# QuadWing_2x2.net
KiCad netlist of a schematic drawn in EAGLE
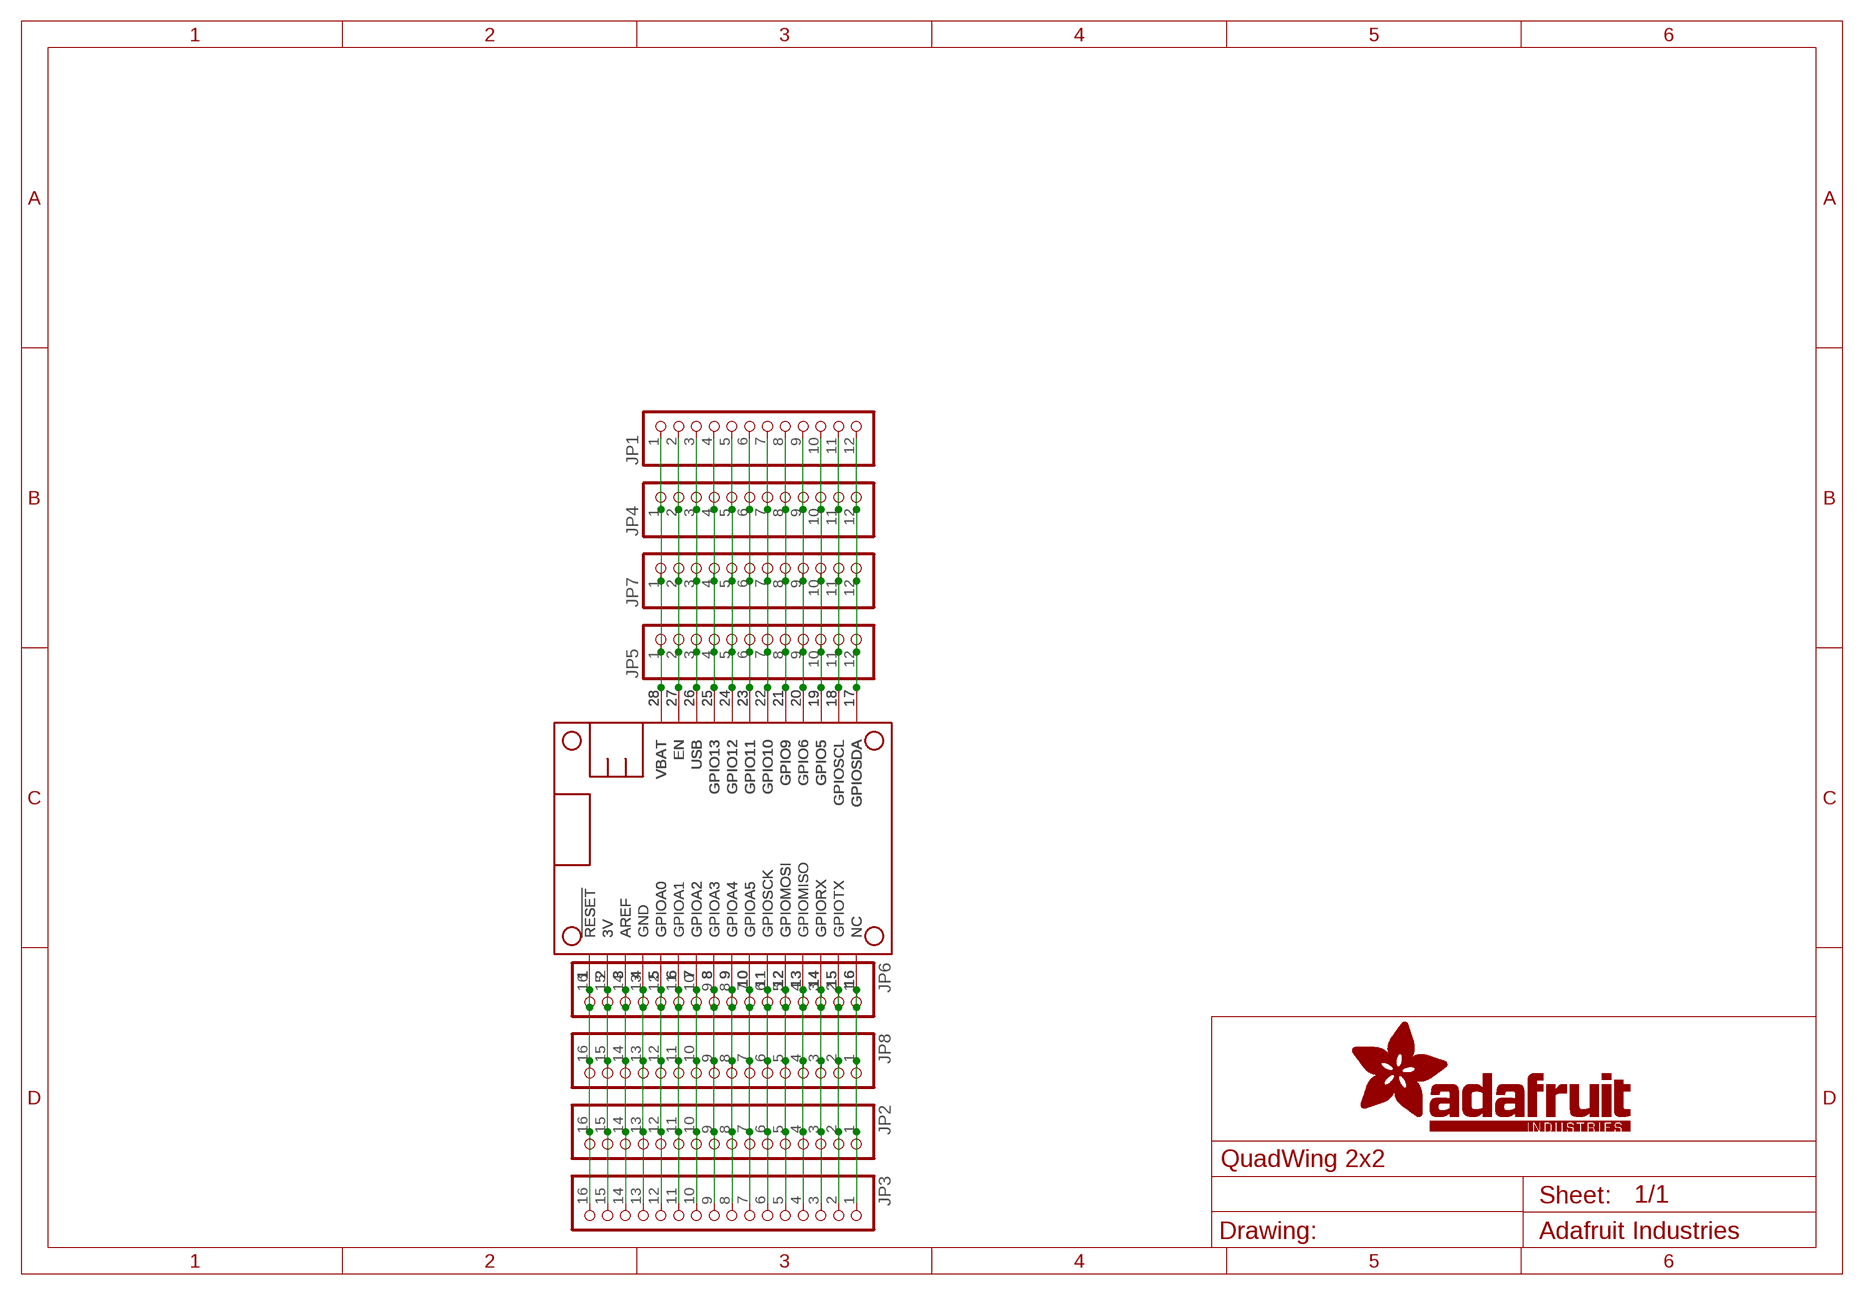
[diagram p0: schematic, sheet 1]

(export (version "E")
  (design (tool "Eeschema 10.0.6"))
  (components
    (comp (ref "JP1")
      (value "HEADER-1X1276MIL")
      (footprint "eagle-import:1X12_ROUND_76MIL")
      (libsource (lib "eagle-import") (part "HEADER-1X1276MIL"))
    )
    (comp (ref "JP2")
      (value "HEADER-1X16_76MIL")
      (footprint "eagle-import:1X16_ROUND_76MIL")
      (libsource (lib "eagle-import") (part "HEADER-1X16_76MIL"))
    )
    (comp (ref "JP3")
      (value "HEADER-1X16_76MIL")
      (footprint "eagle-import:1X16_ROUND_76MIL")
      (libsource (lib "eagle-import") (part "HEADER-1X16_76MIL"))
    )
    (comp (ref "JP4")
      (value "HEADER-1X1276MIL")
      (footprint "eagle-import:1X12_ROUND_76MIL")
      (libsource (lib "eagle-import") (part "HEADER-1X1276MIL"))
    )
    (comp (ref "JP5")
      (value "HEADER-1X1276MIL")
      (footprint "eagle-import:1X12_ROUND_76MIL")
      (libsource (lib "eagle-import") (part "HEADER-1X1276MIL"))
    )
    (comp (ref "JP6")
      (value "HEADER-1X16_76MIL")
      (footprint "eagle-import:1X16_ROUND_76MIL")
      (libsource (lib "eagle-import") (part "HEADER-1X16_76MIL"))
    )
    (comp (ref "JP7")
      (value "HEADER-1X1276MIL")
      (footprint "eagle-import:1X12_ROUND_76MIL")
      (libsource (lib "eagle-import") (part "HEADER-1X1276MIL"))
    )
    (comp (ref "JP8")
      (value "HEADER-1X16_76MIL")
      (footprint "eagle-import:1X16_ROUND_76MIL")
      (libsource (lib "eagle-import") (part "HEADER-1X16_76MIL"))
    )
    (comp (ref "MS1")
      (value "FEATHERWING_NODIM")
      (footprint "eagle-import:FEATHERWING_DIM")
      (libsource (lib "eagle-import") (part "FEATHERWING_NODIM"))
    )
    (comp (ref "MS2")
      (value "FEATHERWING_NODIM")
      (footprint "eagle-import:FEATHERWING_DIM")
      (libsource (lib "eagle-import") (part "FEATHERWING_NODIM"))
    )
    (comp (ref "MS3")
      (value "FEATHERWING_NODIM")
      (footprint "eagle-import:FEATHERWING_DIM")
      (libsource (lib "eagle-import") (part "FEATHERWING_NODIM"))
    )
    (comp (ref "MS4")
      (value "FEATHERWING_NODIM")
      (footprint "eagle-import:FEATHERWING_DIM")
      (libsource (lib "eagle-import") (part "FEATHERWING_NODIM"))
    )
  )
  (nets
    (net (code "1") (name "Net-(MS1-3V)") (class "Default")
      (node (ref "JP2") (pin "15") (pinfunction "15_15") (pintype "passive"))
      (node (ref "JP3") (pin "15") (pinfunction "15_15") (pintype "passive"))
      (node (ref "JP6") (pin "15") (pinfunction "15_15") (pintype "passive"))
      (node (ref "JP8") (pin "15") (pinfunction "15_15") (pintype "passive"))
      (node (ref "MS1") (pin "2") (pinfunction "3V_2") (pintype "power_in"))
      (node (ref "MS2") (pin "2") (pinfunction "3V_2") (pintype "power_in"))
      (node (ref "MS3") (pin "2") (pinfunction "3V_2") (pintype "power_in"))
      (node (ref "MS4") (pin "2") (pinfunction "3V_2") (pintype "power_in"))
    )
    (net (code "2") (name "Net-(MS1-AREF)") (class "Default")
      (node (ref "JP2") (pin "14") (pinfunction "14_14") (pintype "passive"))
      (node (ref "JP3") (pin "14") (pinfunction "14_14") (pintype "passive"))
      (node (ref "JP6") (pin "14") (pinfunction "14_14") (pintype "passive"))
      (node (ref "JP8") (pin "14") (pinfunction "14_14") (pintype "passive"))
      (node (ref "MS1") (pin "3") (pinfunction "AREF_3") (pintype "passive"))
      (node (ref "MS2") (pin "3") (pinfunction "AREF_3") (pintype "passive"))
      (node (ref "MS3") (pin "3") (pinfunction "AREF_3") (pintype "passive"))
      (node (ref "MS4") (pin "3") (pinfunction "AREF_3") (pintype "passive"))
    )
    (net (code "3") (name "Net-(MS1-EN)") (class "Default")
      (node (ref "JP1") (pin "2") (pinfunction "2_2") (pintype "passive"))
      (node (ref "JP4") (pin "2") (pinfunction "2_2") (pintype "passive"))
      (node (ref "JP5") (pin "2") (pinfunction "2_2") (pintype "passive"))
      (node (ref "JP7") (pin "2") (pinfunction "2_2") (pintype "passive"))
      (node (ref "MS1") (pin "27") (pinfunction "EN_27") (pintype "passive"))
      (node (ref "MS2") (pin "27") (pinfunction "EN_27") (pintype "passive"))
      (node (ref "MS3") (pin "27") (pinfunction "EN_27") (pintype "passive"))
      (node (ref "MS4") (pin "27") (pinfunction "EN_27") (pintype "passive"))
    )
    (net (code "4") (name "Net-(MS1-GND)") (class "Default")
      (node (ref "JP2") (pin "13") (pinfunction "13_13") (pintype "passive"))
      (node (ref "JP3") (pin "13") (pinfunction "13_13") (pintype "passive"))
      (node (ref "JP6") (pin "13") (pinfunction "13_13") (pintype "passive"))
      (node (ref "JP8") (pin "13") (pinfunction "13_13") (pintype "passive"))
      (node (ref "MS1") (pin "4") (pinfunction "GND_4") (pintype "power_in"))
      (node (ref "MS2") (pin "4") (pinfunction "GND_4") (pintype "power_in"))
      (node (ref "MS3") (pin "4") (pinfunction "GND_4") (pintype "power_in"))
      (node (ref "MS4") (pin "4") (pinfunction "GND_4") (pintype "power_in"))
    )
    (net (code "5") (name "Net-(MS1-GPIO5)") (class "Default")
      (node (ref "JP1") (pin "10") (pinfunction "10_10") (pintype "passive"))
      (node (ref "JP4") (pin "10") (pinfunction "10_10") (pintype "passive"))
      (node (ref "JP5") (pin "10") (pinfunction "10_10") (pintype "passive"))
      (node (ref "JP7") (pin "10") (pinfunction "10_10") (pintype "passive"))
      (node (ref "MS1") (pin "19") (pinfunction "GPIO5_19") (pintype "bidirectional"))
      (node (ref "MS2") (pin "19") (pinfunction "GPIO5_19") (pintype "bidirectional"))
      (node (ref "MS3") (pin "19") (pinfunction "GPIO5_19") (pintype "bidirectional"))
      (node (ref "MS4") (pin "19") (pinfunction "GPIO5_19") (pintype "bidirectional"))
    )
    (net (code "6") (name "Net-(MS1-GPIO6)") (class "Default")
      (node (ref "JP1") (pin "9") (pinfunction "9_9") (pintype "passive"))
      (node (ref "JP4") (pin "9") (pinfunction "9_9") (pintype "passive"))
      (node (ref "JP5") (pin "9") (pinfunction "9_9") (pintype "passive"))
      (node (ref "JP7") (pin "9") (pinfunction "9_9") (pintype "passive"))
      (node (ref "MS1") (pin "20") (pinfunction "GPIO6_20") (pintype "bidirectional"))
      (node (ref "MS2") (pin "20") (pinfunction "GPIO6_20") (pintype "bidirectional"))
      (node (ref "MS3") (pin "20") (pinfunction "GPIO6_20") (pintype "bidirectional"))
      (node (ref "MS4") (pin "20") (pinfunction "GPIO6_20") (pintype "bidirectional"))
    )
    (net (code "7") (name "Net-(MS1-GPIO9)") (class "Default")
      (node (ref "JP1") (pin "8") (pinfunction "8_8") (pintype "passive"))
      (node (ref "JP4") (pin "8") (pinfunction "8_8") (pintype "passive"))
      (node (ref "JP5") (pin "8") (pinfunction "8_8") (pintype "passive"))
      (node (ref "JP7") (pin "8") (pinfunction "8_8") (pintype "passive"))
      (node (ref "MS1") (pin "21") (pinfunction "GPIO9_21") (pintype "bidirectional"))
      (node (ref "MS2") (pin "21") (pinfunction "GPIO9_21") (pintype "bidirectional"))
      (node (ref "MS3") (pin "21") (pinfunction "GPIO9_21") (pintype "bidirectional"))
      (node (ref "MS4") (pin "21") (pinfunction "GPIO9_21") (pintype "bidirectional"))
    )
    (net (code "8") (name "Net-(MS1-GPIO10)") (class "Default")
      (node (ref "JP1") (pin "7") (pinfunction "7_7") (pintype "passive"))
      (node (ref "JP4") (pin "7") (pinfunction "7_7") (pintype "passive"))
      (node (ref "JP5") (pin "7") (pinfunction "7_7") (pintype "passive"))
      (node (ref "JP7") (pin "7") (pinfunction "7_7") (pintype "passive"))
      (node (ref "MS1") (pin "22") (pinfunction "GPIO10_22") (pintype "bidirectional"))
      (node (ref "MS2") (pin "22") (pinfunction "GPIO10_22") (pintype "bidirectional"))
      (node (ref "MS3") (pin "22") (pinfunction "GPIO10_22") (pintype "bidirectional"))
      (node (ref "MS4") (pin "22") (pinfunction "GPIO10_22") (pintype "bidirectional"))
    )
    (net (code "9") (name "Net-(MS1-GPIO11)") (class "Default")
      (node (ref "JP1") (pin "6") (pinfunction "6_6") (pintype "passive"))
      (node (ref "JP4") (pin "6") (pinfunction "6_6") (pintype "passive"))
      (node (ref "JP5") (pin "6") (pinfunction "6_6") (pintype "passive"))
      (node (ref "JP7") (pin "6") (pinfunction "6_6") (pintype "passive"))
      (node (ref "MS1") (pin "23") (pinfunction "GPIO11_23") (pintype "bidirectional"))
      (node (ref "MS2") (pin "23") (pinfunction "GPIO11_23") (pintype "bidirectional"))
      (node (ref "MS3") (pin "23") (pinfunction "GPIO11_23") (pintype "bidirectional"))
      (node (ref "MS4") (pin "23") (pinfunction "GPIO11_23") (pintype "bidirectional"))
    )
    (net (code "10") (name "Net-(MS1-GPIO12)") (class "Default")
      (node (ref "JP1") (pin "5") (pinfunction "5_5") (pintype "passive"))
      (node (ref "JP4") (pin "5") (pinfunction "5_5") (pintype "passive"))
      (node (ref "JP5") (pin "5") (pinfunction "5_5") (pintype "passive"))
      (node (ref "JP7") (pin "5") (pinfunction "5_5") (pintype "passive"))
      (node (ref "MS1") (pin "24") (pinfunction "GPIO12_24") (pintype "bidirectional"))
      (node (ref "MS2") (pin "24") (pinfunction "GPIO12_24") (pintype "bidirectional"))
      (node (ref "MS3") (pin "24") (pinfunction "GPIO12_24") (pintype "bidirectional"))
      (node (ref "MS4") (pin "24") (pinfunction "GPIO12_24") (pintype "bidirectional"))
    )
    (net (code "11") (name "Net-(MS1-GPIO13)") (class "Default")
      (node (ref "JP1") (pin "4") (pinfunction "4_4") (pintype "passive"))
      (node (ref "JP4") (pin "4") (pinfunction "4_4") (pintype "passive"))
      (node (ref "JP5") (pin "4") (pinfunction "4_4") (pintype "passive"))
      (node (ref "JP7") (pin "4") (pinfunction "4_4") (pintype "passive"))
      (node (ref "MS1") (pin "25") (pinfunction "GPIO13_25") (pintype "bidirectional"))
      (node (ref "MS2") (pin "25") (pinfunction "GPIO13_25") (pintype "bidirectional"))
      (node (ref "MS3") (pin "25") (pinfunction "GPIO13_25") (pintype "bidirectional"))
      (node (ref "MS4") (pin "25") (pinfunction "GPIO13_25") (pintype "bidirectional"))
    )
    (net (code "12") (name "Net-(MS1-GPIOA0)") (class "Default")
      (node (ref "JP2") (pin "12") (pinfunction "12_12") (pintype "passive"))
      (node (ref "JP3") (pin "12") (pinfunction "12_12") (pintype "passive"))
      (node (ref "JP6") (pin "12") (pinfunction "12_12") (pintype "passive"))
      (node (ref "JP8") (pin "12") (pinfunction "12_12") (pintype "passive"))
      (node (ref "MS1") (pin "5") (pinfunction "GPIOA0_5") (pintype "bidirectional"))
      (node (ref "MS2") (pin "5") (pinfunction "GPIOA0_5") (pintype "bidirectional"))
      (node (ref "MS3") (pin "5") (pinfunction "GPIOA0_5") (pintype "bidirectional"))
      (node (ref "MS4") (pin "5") (pinfunction "GPIOA0_5") (pintype "bidirectional"))
    )
    (net (code "13") (name "Net-(MS1-GPIOA1)") (class "Default")
      (node (ref "JP2") (pin "11") (pinfunction "11_11") (pintype "passive"))
      (node (ref "JP3") (pin "11") (pinfunction "11_11") (pintype "passive"))
      (node (ref "JP6") (pin "11") (pinfunction "11_11") (pintype "passive"))
      (node (ref "JP8") (pin "11") (pinfunction "11_11") (pintype "passive"))
      (node (ref "MS1") (pin "6") (pinfunction "GPIOA1_6") (pintype "bidirectional"))
      (node (ref "MS2") (pin "6") (pinfunction "GPIOA1_6") (pintype "bidirectional"))
      (node (ref "MS3") (pin "6") (pinfunction "GPIOA1_6") (pintype "bidirectional"))
      (node (ref "MS4") (pin "6") (pinfunction "GPIOA1_6") (pintype "bidirectional"))
    )
    (net (code "14") (name "Net-(MS1-GPIOA2)") (class "Default")
      (node (ref "JP2") (pin "10") (pinfunction "10_10") (pintype "passive"))
      (node (ref "JP3") (pin "10") (pinfunction "10_10") (pintype "passive"))
      (node (ref "JP6") (pin "10") (pinfunction "10_10") (pintype "passive"))
      (node (ref "JP8") (pin "10") (pinfunction "10_10") (pintype "passive"))
      (node (ref "MS1") (pin "7") (pinfunction "GPIOA2_7") (pintype "bidirectional"))
      (node (ref "MS2") (pin "7") (pinfunction "GPIOA2_7") (pintype "bidirectional"))
      (node (ref "MS3") (pin "7") (pinfunction "GPIOA2_7") (pintype "bidirectional"))
      (node (ref "MS4") (pin "7") (pinfunction "GPIOA2_7") (pintype "bidirectional"))
    )
    (net (code "15") (name "Net-(MS1-GPIOA3)") (class "Default")
      (node (ref "JP2") (pin "9") (pinfunction "9_9") (pintype "passive"))
      (node (ref "JP3") (pin "9") (pinfunction "9_9") (pintype "passive"))
      (node (ref "JP6") (pin "9") (pinfunction "9_9") (pintype "passive"))
      (node (ref "JP8") (pin "9") (pinfunction "9_9") (pintype "passive"))
      (node (ref "MS1") (pin "8") (pinfunction "GPIOA3_8") (pintype "bidirectional"))
      (node (ref "MS2") (pin "8") (pinfunction "GPIOA3_8") (pintype "bidirectional"))
      (node (ref "MS3") (pin "8") (pinfunction "GPIOA3_8") (pintype "bidirectional"))
      (node (ref "MS4") (pin "8") (pinfunction "GPIOA3_8") (pintype "bidirectional"))
    )
    (net (code "16") (name "Net-(MS1-GPIOA4)") (class "Default")
      (node (ref "JP2") (pin "8") (pinfunction "8_8") (pintype "passive"))
      (node (ref "JP3") (pin "8") (pinfunction "8_8") (pintype "passive"))
      (node (ref "JP6") (pin "8") (pinfunction "8_8") (pintype "passive"))
      (node (ref "JP8") (pin "8") (pinfunction "8_8") (pintype "passive"))
      (node (ref "MS1") (pin "9") (pinfunction "GPIOA4_9") (pintype "bidirectional"))
      (node (ref "MS2") (pin "9") (pinfunction "GPIOA4_9") (pintype "bidirectional"))
      (node (ref "MS3") (pin "9") (pinfunction "GPIOA4_9") (pintype "bidirectional"))
      (node (ref "MS4") (pin "9") (pinfunction "GPIOA4_9") (pintype "bidirectional"))
    )
    (net (code "17") (name "Net-(MS1-GPIOA5)") (class "Default")
      (node (ref "JP2") (pin "7") (pinfunction "7_7") (pintype "passive"))
      (node (ref "JP3") (pin "7") (pinfunction "7_7") (pintype "passive"))
      (node (ref "JP6") (pin "7") (pinfunction "7_7") (pintype "passive"))
      (node (ref "JP8") (pin "7") (pinfunction "7_7") (pintype "passive"))
      (node (ref "MS1") (pin "10") (pinfunction "GPIOA5_10") (pintype "bidirectional"))
      (node (ref "MS2") (pin "10") (pinfunction "GPIOA5_10") (pintype "bidirectional"))
      (node (ref "MS3") (pin "10") (pinfunction "GPIOA5_10") (pintype "bidirectional"))
      (node (ref "MS4") (pin "10") (pinfunction "GPIOA5_10") (pintype "bidirectional"))
    )
    (net (code "18") (name "Net-(MS1-GPIOMISO)") (class "Default")
      (node (ref "JP2") (pin "4") (pinfunction "4_4") (pintype "passive"))
      (node (ref "JP3") (pin "4") (pinfunction "4_4") (pintype "passive"))
      (node (ref "JP6") (pin "4") (pinfunction "4_4") (pintype "passive"))
      (node (ref "JP8") (pin "4") (pinfunction "4_4") (pintype "passive"))
      (node (ref "MS1") (pin "13") (pinfunction "GPIOMISO_13") (pintype "bidirectional"))
      (node (ref "MS2") (pin "13") (pinfunction "GPIOMISO_13") (pintype "bidirectional"))
      (node (ref "MS3") (pin "13") (pinfunction "GPIOMISO_13") (pintype "bidirectional"))
      (node (ref "MS4") (pin "13") (pinfunction "GPIOMISO_13") (pintype "bidirectional"))
    )
    (net (code "19") (name "Net-(MS1-GPIOMOSI)") (class "Default")
      (node (ref "JP2") (pin "5") (pinfunction "5_5") (pintype "passive"))
      (node (ref "JP3") (pin "5") (pinfunction "5_5") (pintype "passive"))
      (node (ref "JP6") (pin "5") (pinfunction "5_5") (pintype "passive"))
      (node (ref "JP8") (pin "5") (pinfunction "5_5") (pintype "passive"))
      (node (ref "MS1") (pin "12") (pinfunction "GPIOMOSI_12") (pintype "bidirectional"))
      (node (ref "MS2") (pin "12") (pinfunction "GPIOMOSI_12") (pintype "bidirectional"))
      (node (ref "MS3") (pin "12") (pinfunction "GPIOMOSI_12") (pintype "bidirectional"))
      (node (ref "MS4") (pin "12") (pinfunction "GPIOMOSI_12") (pintype "bidirectional"))
    )
    (net (code "20") (name "Net-(MS1-GPIORX)") (class "Default")
      (node (ref "JP2") (pin "3") (pinfunction "3_3") (pintype "passive"))
      (node (ref "JP3") (pin "3") (pinfunction "3_3") (pintype "passive"))
      (node (ref "JP6") (pin "3") (pinfunction "3_3") (pintype "passive"))
      (node (ref "JP8") (pin "3") (pinfunction "3_3") (pintype "passive"))
      (node (ref "MS1") (pin "14") (pinfunction "GPIORX_14") (pintype "bidirectional"))
      (node (ref "MS2") (pin "14") (pinfunction "GPIORX_14") (pintype "bidirectional"))
      (node (ref "MS3") (pin "14") (pinfunction "GPIORX_14") (pintype "bidirectional"))
      (node (ref "MS4") (pin "14") (pinfunction "GPIORX_14") (pintype "bidirectional"))
    )
    (net (code "21") (name "Net-(MS1-GPIOSCK)") (class "Default")
      (node (ref "JP2") (pin "6") (pinfunction "6_6") (pintype "passive"))
      (node (ref "JP3") (pin "6") (pinfunction "6_6") (pintype "passive"))
      (node (ref "JP6") (pin "6") (pinfunction "6_6") (pintype "passive"))
      (node (ref "JP8") (pin "6") (pinfunction "6_6") (pintype "passive"))
      (node (ref "MS1") (pin "11") (pinfunction "GPIOSCK_11") (pintype "bidirectional"))
      (node (ref "MS2") (pin "11") (pinfunction "GPIOSCK_11") (pintype "bidirectional"))
      (node (ref "MS3") (pin "11") (pinfunction "GPIOSCK_11") (pintype "bidirectional"))
      (node (ref "MS4") (pin "11") (pinfunction "GPIOSCK_11") (pintype "bidirectional"))
    )
    (net (code "22") (name "Net-(MS1-GPIOSCL)") (class "Default")
      (node (ref "JP1") (pin "11") (pinfunction "11_11") (pintype "passive"))
      (node (ref "JP4") (pin "11") (pinfunction "11_11") (pintype "passive"))
      (node (ref "JP5") (pin "11") (pinfunction "11_11") (pintype "passive"))
      (node (ref "JP7") (pin "11") (pinfunction "11_11") (pintype "passive"))
      (node (ref "MS1") (pin "18") (pinfunction "GPIOSCL_18") (pintype "bidirectional"))
      (node (ref "MS2") (pin "18") (pinfunction "GPIOSCL_18") (pintype "bidirectional"))
      (node (ref "MS3") (pin "18") (pinfunction "GPIOSCL_18") (pintype "bidirectional"))
      (node (ref "MS4") (pin "18") (pinfunction "GPIOSCL_18") (pintype "bidirectional"))
    )
    (net (code "23") (name "Net-(MS1-GPIOSDA)") (class "Default")
      (node (ref "JP1") (pin "12") (pinfunction "12_12") (pintype "passive"))
      (node (ref "JP4") (pin "12") (pinfunction "12_12") (pintype "passive"))
      (node (ref "JP5") (pin "12") (pinfunction "12_12") (pintype "passive"))
      (node (ref "JP7") (pin "12") (pinfunction "12_12") (pintype "passive"))
      (node (ref "MS1") (pin "17") (pinfunction "GPIOSDA_17") (pintype "bidirectional"))
      (node (ref "MS2") (pin "17") (pinfunction "GPIOSDA_17") (pintype "bidirectional"))
      (node (ref "MS3") (pin "17") (pinfunction "GPIOSDA_17") (pintype "bidirectional"))
      (node (ref "MS4") (pin "17") (pinfunction "GPIOSDA_17") (pintype "bidirectional"))
    )
    (net (code "24") (name "Net-(MS1-GPIOTX)") (class "Default")
      (node (ref "JP2") (pin "2") (pinfunction "2_2") (pintype "passive"))
      (node (ref "JP3") (pin "2") (pinfunction "2_2") (pintype "passive"))
      (node (ref "JP6") (pin "2") (pinfunction "2_2") (pintype "passive"))
      (node (ref "JP8") (pin "2") (pinfunction "2_2") (pintype "passive"))
      (node (ref "MS1") (pin "15") (pinfunction "GPIOTX_15") (pintype "bidirectional"))
      (node (ref "MS2") (pin "15") (pinfunction "GPIOTX_15") (pintype "bidirectional"))
      (node (ref "MS3") (pin "15") (pinfunction "GPIOTX_15") (pintype "bidirectional"))
      (node (ref "MS4") (pin "15") (pinfunction "GPIOTX_15") (pintype "bidirectional"))
    )
    (net (code "25") (name "Net-(MS1-NC)") (class "Default")
      (node (ref "JP2") (pin "1") (pinfunction "1_1") (pintype "passive"))
      (node (ref "JP3") (pin "1") (pinfunction "1_1") (pintype "passive"))
      (node (ref "JP6") (pin "1") (pinfunction "1_1") (pintype "passive"))
      (node (ref "JP8") (pin "1") (pinfunction "1_1") (pintype "passive"))
      (node (ref "MS1") (pin "16") (pinfunction "NC_16") (pintype "passive"))
      (node (ref "MS2") (pin "16") (pinfunction "NC_16") (pintype "passive"))
      (node (ref "MS3") (pin "16") (pinfunction "NC_16") (pintype "passive"))
      (node (ref "MS4") (pin "16") (pinfunction "NC_16") (pintype "passive"))
    )
    (net (code "26") (name "Net-(MS1-USB)") (class "Default")
      (node (ref "JP1") (pin "3") (pinfunction "3_3") (pintype "passive"))
      (node (ref "JP4") (pin "3") (pinfunction "3_3") (pintype "passive"))
      (node (ref "JP5") (pin "3") (pinfunction "3_3") (pintype "passive"))
      (node (ref "JP7") (pin "3") (pinfunction "3_3") (pintype "passive"))
      (node (ref "MS1") (pin "26") (pinfunction "USB_26") (pintype "power_in"))
      (node (ref "MS2") (pin "26") (pinfunction "USB_26") (pintype "power_in"))
      (node (ref "MS3") (pin "26") (pinfunction "USB_26") (pintype "power_in"))
      (node (ref "MS4") (pin "26") (pinfunction "USB_26") (pintype "power_in"))
    )
    (net (code "27") (name "Net-(MS1-VBAT)") (class "Default")
      (node (ref "JP1") (pin "1") (pinfunction "1_1") (pintype "passive"))
      (node (ref "JP4") (pin "1") (pinfunction "1_1") (pintype "passive"))
      (node (ref "JP5") (pin "1") (pinfunction "1_1") (pintype "passive"))
      (node (ref "JP7") (pin "1") (pinfunction "1_1") (pintype "passive"))
      (node (ref "MS1") (pin "28") (pinfunction "VBAT_28") (pintype "power_in"))
      (node (ref "MS2") (pin "28") (pinfunction "VBAT_28") (pintype "power_in"))
      (node (ref "MS3") (pin "28") (pinfunction "VBAT_28") (pintype "power_in"))
      (node (ref "MS4") (pin "28") (pinfunction "VBAT_28") (pintype "power_in"))
    )
    (net (code "28") (name "Net-(MS1-~{RESET})") (class "Default")
      (node (ref "JP2") (pin "16") (pinfunction "16_16") (pintype "passive"))
      (node (ref "JP3") (pin "16") (pinfunction "16_16") (pintype "passive"))
      (node (ref "JP6") (pin "16") (pinfunction "16_16") (pintype "passive"))
      (node (ref "JP8") (pin "16") (pinfunction "16_16") (pintype "passive"))
      (node (ref "MS1") (pin "1") (pinfunction "~{RESET}_1") (pintype "input"))
      (node (ref "MS2") (pin "1") (pinfunction "~{RESET}_1") (pintype "input"))
      (node (ref "MS3") (pin "1") (pinfunction "~{RESET}_1") (pintype "input"))
      (node (ref "MS4") (pin "1") (pinfunction "~{RESET}_1") (pintype "input"))
    )
  )
)
